# New_Multirotor_CPU_imu_V1_2.net
KiCad netlist of a schematic drawn in EAGLE
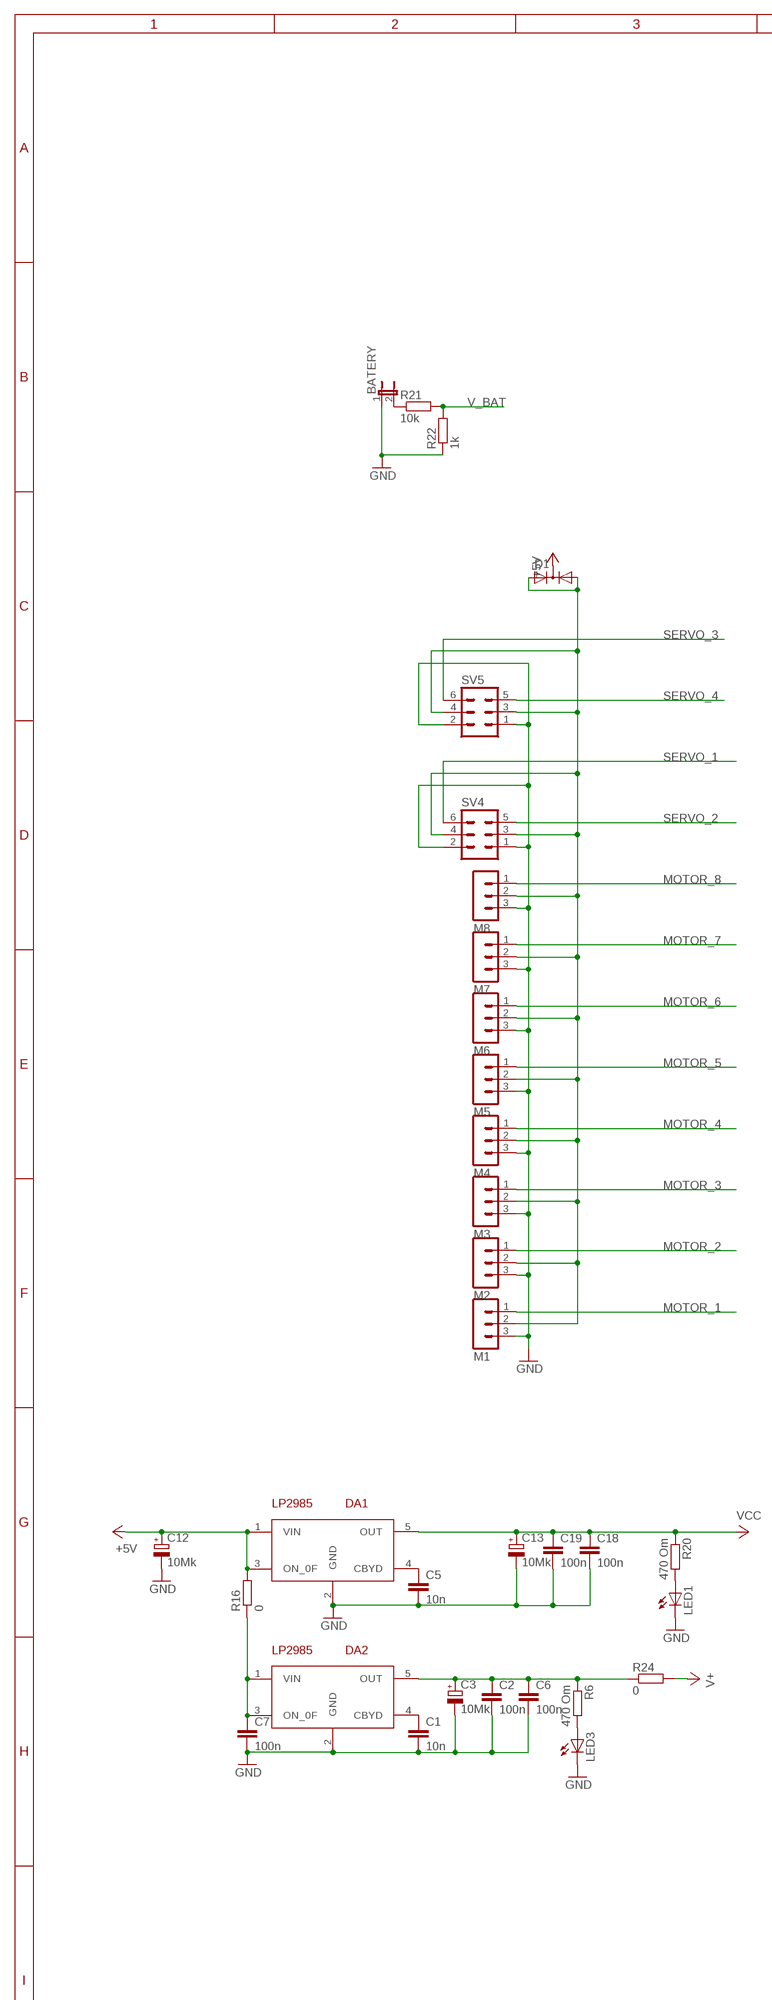
[diagram p0: schematic, sheet 1, part 1 of 2]
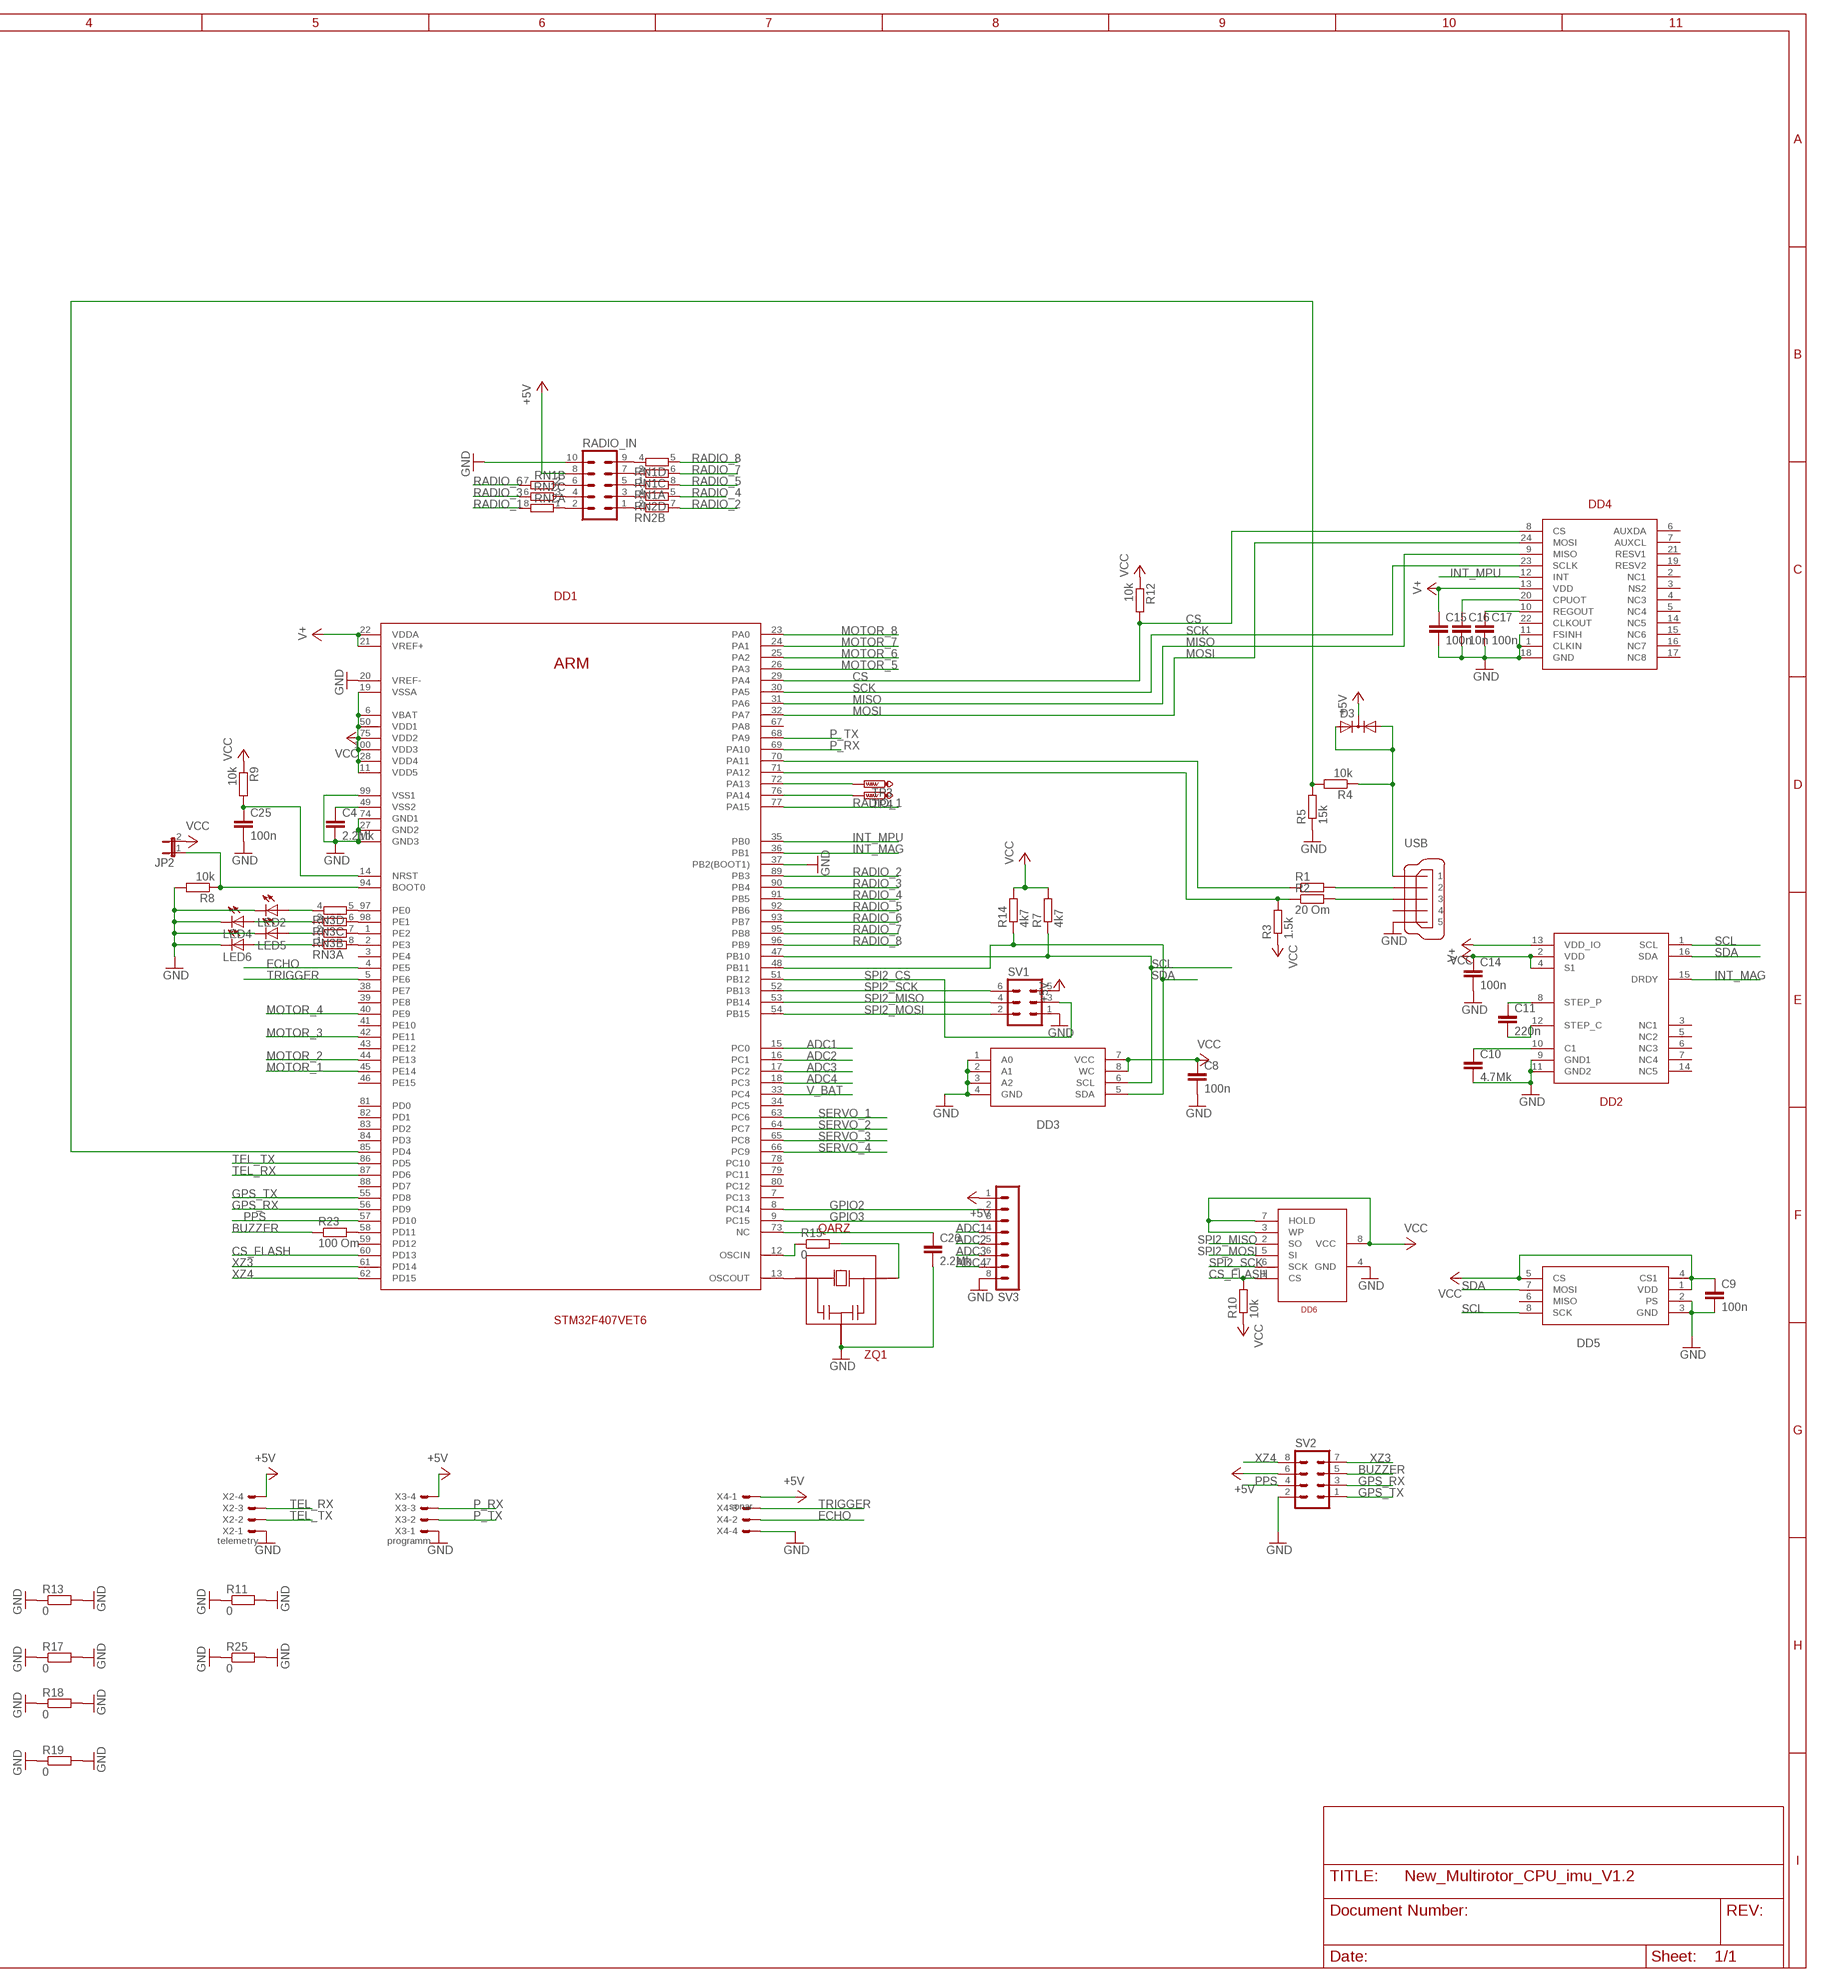
[diagram p1: schematic, sheet 1, part 2 of 2]

(export (version "E")
  (design (tool "Eeschema 10.0.6"))
  (components
    (comp (ref "BATERY")
      (value "JP1E")
      (footprint "eagle-import:JP1")
      (libsource (lib "eagle-import") (part "JP1E"))
    )
    (comp (ref "C1")
      (value "10n")
      (footprint "eagle-import:C0603K")
      (libsource (lib "eagle-import") (part "C-EUC0603K"))
    )
    (comp (ref "C2")
      (value "100n")
      (footprint "eagle-import:C0603K")
      (libsource (lib "eagle-import") (part "C-EUC0603K"))
    )
    (comp (ref "C3")
      (value "10Mk")
      (footprint "eagle-import:A_3216-18W")
      (libsource (lib "eagle-import") (part "CPOL-EUA/3216-18W"))
    )
    (comp (ref "C4")
      (value "2.2Mk")
      (footprint "eagle-import:C0603K")
      (libsource (lib "eagle-import") (part "C-EUC0603K"))
    )
    (comp (ref "C5")
      (value "10n")
      (footprint "eagle-import:C0603K")
      (libsource (lib "eagle-import") (part "C-EUC0603K"))
    )
    (comp (ref "C6")
      (value "100n")
      (footprint "eagle-import:C0603K")
      (libsource (lib "eagle-import") (part "C-EUC0603K"))
    )
    (comp (ref "C7")
      (value "100n")
      (footprint "eagle-import:C0603K")
      (libsource (lib "eagle-import") (part "C-EUC0603K"))
    )
    (comp (ref "C8")
      (value "100n")
      (footprint "eagle-import:C0603K")
      (libsource (lib "eagle-import") (part "C-EUC0603K"))
    )
    (comp (ref "C9")
      (value "100n")
      (footprint "eagle-import:C0603K")
      (libsource (lib "eagle-import") (part "C-EUC0603K"))
    )
    (comp (ref "C10")
      (value "4.7Mk")
      (footprint "eagle-import:C0603K")
      (libsource (lib "eagle-import") (part "C-EUC0603K"))
    )
    (comp (ref "C11")
      (value "220n")
      (footprint "eagle-import:C0603K")
      (libsource (lib "eagle-import") (part "C-EUC0603K"))
    )
    (comp (ref "C12")
      (value "10Mk")
      (footprint "eagle-import:A_3216-18W")
      (libsource (lib "eagle-import") (part "CPOL-EUA/3216-18W"))
    )
    (comp (ref "C13")
      (value "10Mk")
      (footprint "eagle-import:A_3216-18W")
      (libsource (lib "eagle-import") (part "CPOL-EUA/3216-18W"))
    )
    (comp (ref "C14")
      (value "100n")
      (footprint "eagle-import:C0603K")
      (libsource (lib "eagle-import") (part "C-EUC0603K"))
    )
    (comp (ref "C15")
      (value "100n")
      (footprint "eagle-import:C0603K")
      (libsource (lib "eagle-import") (part "C-EUC0603K"))
    )
    (comp (ref "C16")
      (value "10n")
      (footprint "eagle-import:C0603K")
      (libsource (lib "eagle-import") (part "C-EUC0603K"))
    )
    (comp (ref "C17")
      (value "100n")
      (footprint "eagle-import:C0603K")
      (libsource (lib "eagle-import") (part "C-EUC0603K"))
    )
    (comp (ref "C18")
      (value "100n")
      (footprint "eagle-import:C0603K")
      (libsource (lib "eagle-import") (part "C-EUC0603K"))
    )
    (comp (ref "C19")
      (value "100n")
      (footprint "eagle-import:C0603K")
      (libsource (lib "eagle-import") (part "C-EUC0603K"))
    )
    (comp (ref "C25")
      (value "100n")
      (footprint "eagle-import:C0603K")
      (libsource (lib "eagle-import") (part "C-EUC0603K"))
    )
    (comp (ref "C26")
      (value "2.2Mk")
      (footprint "eagle-import:C0603K")
      (libsource (lib "eagle-import") (part "C-EUC0603K"))
    )
    (comp (ref "D1")
      (value "DIODE-2AC|CASOT23")
      (footprint "eagle-import:SOT23")
      (libsource (lib "eagle-import") (part "DIODE-2AC|CASOT23"))
    )
    (comp (ref "D3")
      (value "DIODE-2AC|CASOT23")
      (footprint "eagle-import:SOT23")
      (libsource (lib "eagle-import") (part "DIODE-2AC|CASOT23"))
    )
    (comp (ref "DA1")
      (value "LP2985")
      (footprint "eagle-import:SOT23-5L")
      (libsource (lib "eagle-import") (part "3.3"))
    )
    (comp (ref "DA2")
      (value "LP2985")
      (footprint "eagle-import:SOT23-5L")
      (libsource (lib "eagle-import") (part "3.3"))
    )
    (comp (ref "DD1")
      (value "STM32F407VET6")
      (footprint "eagle-import:LQFP100")
      (libsource (lib "eagle-import") (part "STM32F407VET6"))
    )
    (comp (ref "DD2")
      (value "HMC5883L")
      (footprint "eagle-import:LCC-16")
      (libsource (lib "eagle-import") (part "HMC5883L"))
    )
    (comp (ref "DD3")
      (value "24C512")
      (footprint "eagle-import:SOIC8")
      (libsource (lib "eagle-import") (part "24C512"))
    )
    (comp (ref "DD4")
      (value "MPU6000")
      (footprint "eagle-import:JEDEC")
      (libsource (lib "eagle-import") (part "MPU6000"))
    )
    (comp (ref "DD5")
      (value "MS5611-01BA03")
      (footprint "eagle-import:MS5611-01BA03")
      (libsource (lib "eagle-import") (part "MS5611-01BA03"))
    )
    (comp (ref "DD6")
      (value "W25X40")
      (footprint "eagle-import:SOIC8")
      (libsource (lib "eagle-import") (part "W25X40"))
    )
    (comp (ref "JP2")
      (value "JP1E")
      (footprint "eagle-import:JP1")
      (libsource (lib "eagle-import") (part "JP1E"))
    )
    (comp (ref "LED1")
      (value "LEDCHIPLED_0603")
      (footprint "eagle-import:CHIPLED_0603")
      (libsource (lib "eagle-import") (part "LEDCHIPLED_0603"))
    )
    (comp (ref "LED2")
      (value "LEDCHIPLED_0603")
      (footprint "eagle-import:CHIPLED_0603")
      (libsource (lib "eagle-import") (part "LEDCHIPLED_0603"))
    )
    (comp (ref "LED3")
      (value "LEDCHIPLED_0603")
      (footprint "eagle-import:CHIPLED_0603")
      (libsource (lib "eagle-import") (part "LEDCHIPLED_0603"))
    )
    (comp (ref "LED4")
      (value "LEDCHIPLED_0603")
      (footprint "eagle-import:CHIPLED_0603")
      (libsource (lib "eagle-import") (part "LEDCHIPLED_0603"))
    )
    (comp (ref "LED5")
      (value "LEDCHIPLED_0603")
      (footprint "eagle-import:CHIPLED_0603")
      (libsource (lib "eagle-import") (part "LEDCHIPLED_0603"))
    )
    (comp (ref "LED6")
      (value "LEDCHIPLED_0603")
      (footprint "eagle-import:CHIPLED_0603")
      (libsource (lib "eagle-import") (part "LEDCHIPLED_0603"))
    )
    (comp (ref "M1")
      (value "MA03-1")
      (footprint "eagle-import:MA03-1")
      (fields (field (name "OC_FARNELL") "unknown") (field (name "OC_NEWARK") "unknown"))
      (libsource (lib "eagle-import") (part "MA03-1"))
    )
    (comp (ref "M2")
      (value "MA03-1")
      (footprint "eagle-import:MA03-1")
      (fields (field (name "OC_FARNELL") "unknown") (field (name "OC_NEWARK") "unknown"))
      (libsource (lib "eagle-import") (part "MA03-1"))
    )
    (comp (ref "M3")
      (value "MA03-1")
      (footprint "eagle-import:MA03-1")
      (fields (field (name "OC_FARNELL") "unknown") (field (name "OC_NEWARK") "unknown"))
      (libsource (lib "eagle-import") (part "MA03-1"))
    )
    (comp (ref "M4")
      (value "MA03-1")
      (footprint "eagle-import:MA03-1")
      (fields (field (name "OC_FARNELL") "unknown") (field (name "OC_NEWARK") "unknown"))
      (libsource (lib "eagle-import") (part "MA03-1"))
    )
    (comp (ref "M5")
      (value "MA03-1")
      (footprint "eagle-import:MA03-1")
      (fields (field (name "OC_FARNELL") "unknown") (field (name "OC_NEWARK") "unknown"))
      (libsource (lib "eagle-import") (part "MA03-1"))
    )
    (comp (ref "M6")
      (value "MA03-1")
      (footprint "eagle-import:MA03-1")
      (fields (field (name "OC_FARNELL") "unknown") (field (name "OC_NEWARK") "unknown"))
      (libsource (lib "eagle-import") (part "MA03-1"))
    )
    (comp (ref "M7")
      (value "MA03-1")
      (footprint "eagle-import:MA03-1")
      (fields (field (name "OC_FARNELL") "unknown") (field (name "OC_NEWARK") "unknown"))
      (libsource (lib "eagle-import") (part "MA03-1"))
    )
    (comp (ref "M8")
      (value "MA03-1")
      (footprint "eagle-import:MA03-1")
      (fields (field (name "OC_FARNELL") "unknown") (field (name "OC_NEWARK") "unknown"))
      (libsource (lib "eagle-import") (part "MA03-1"))
    )
    (comp (ref "R1")
      (value "R-EU_R0603")
      (footprint "eagle-import:R0603")
      (libsource (lib "eagle-import") (part "R-EU_R0603"))
    )
    (comp (ref "R2")
      (value "20 Om")
      (footprint "eagle-import:R0603")
      (libsource (lib "eagle-import") (part "R-EU_R0603"))
    )
    (comp (ref "R3")
      (value "1.5k")
      (footprint "eagle-import:R0603")
      (libsource (lib "eagle-import") (part "R-EU_R0603"))
    )
    (comp (ref "R4")
      (value "10k")
      (footprint "eagle-import:R0603")
      (libsource (lib "eagle-import") (part "R-EU_R0603"))
    )
    (comp (ref "R5")
      (value "15k")
      (footprint "eagle-import:R0603")
      (libsource (lib "eagle-import") (part "R-EU_R0603"))
    )
    (comp (ref "R6")
      (value "470 Om")
      (footprint "eagle-import:R0603")
      (libsource (lib "eagle-import") (part "R-EU_R0603"))
    )
    (comp (ref "R7")
      (value "4k7")
      (footprint "eagle-import:R0603")
      (libsource (lib "eagle-import") (part "R-EU_R0603"))
    )
    (comp (ref "R8")
      (value "10k")
      (footprint "eagle-import:R0603")
      (libsource (lib "eagle-import") (part "R-EU_R0603"))
    )
    (comp (ref "R9")
      (value "10k")
      (footprint "eagle-import:R0603")
      (libsource (lib "eagle-import") (part "R-EU_R0603"))
    )
    (comp (ref "R10")
      (value "10k")
      (footprint "eagle-import:R0603")
      (libsource (lib "eagle-import") (part "R-EU_R0603"))
    )
    (comp (ref "R11")
      (value "0")
      (footprint "eagle-import:R0603")
      (libsource (lib "eagle-import") (part "R-EU_R0603"))
    )
    (comp (ref "R12")
      (value "10k")
      (footprint "eagle-import:R0603")
      (libsource (lib "eagle-import") (part "R-EU_R0603"))
    )
    (comp (ref "R13")
      (value "0")
      (footprint "eagle-import:R0603")
      (libsource (lib "eagle-import") (part "R-EU_R0603"))
    )
    (comp (ref "R14")
      (value "4k7")
      (footprint "eagle-import:R0603")
      (libsource (lib "eagle-import") (part "R-EU_R0603"))
    )
    (comp (ref "R15")
      (value "0")
      (footprint "eagle-import:R0603")
      (libsource (lib "eagle-import") (part "R-EU_R0603"))
    )
    (comp (ref "R16")
      (value "0")
      (footprint "eagle-import:R0603")
      (libsource (lib "eagle-import") (part "R-EU_R0603"))
    )
    (comp (ref "R17")
      (value "0")
      (footprint "eagle-import:R0603")
      (libsource (lib "eagle-import") (part "R-EU_R0603"))
    )
    (comp (ref "R18")
      (value "0")
      (footprint "eagle-import:R0603")
      (libsource (lib "eagle-import") (part "R-EU_R0603"))
    )
    (comp (ref "R19")
      (value "0")
      (footprint "eagle-import:R0603")
      (libsource (lib "eagle-import") (part "R-EU_R0603"))
    )
    (comp (ref "R20")
      (value "470 Om")
      (footprint "eagle-import:R0603")
      (libsource (lib "eagle-import") (part "R-EU_R0603"))
    )
    (comp (ref "R21")
      (value "10k")
      (footprint "eagle-import:R0603")
      (libsource (lib "eagle-import") (part "R-EU_R0603"))
    )
    (comp (ref "R22")
      (value "1k")
      (footprint "eagle-import:R0603")
      (libsource (lib "eagle-import") (part "R-EU_R0603"))
    )
    (comp (ref "R23")
      (value "100 Om")
      (footprint "eagle-import:R0603")
      (libsource (lib "eagle-import") (part "R-EU_R0603"))
    )
    (comp (ref "R24")
      (value "0")
      (footprint "eagle-import:R0603")
      (libsource (lib "eagle-import") (part "R-EU_R0603"))
    )
    (comp (ref "R25")
      (value "0")
      (footprint "eagle-import:R0603")
      (libsource (lib "eagle-import") (part "R-EU_R0603"))
    )
    (comp (ref "RADIO_IN")
      (value "MA05-2")
      (footprint "eagle-import:MA05-2")
      (libsource (lib "eagle-import") (part "MA05-2"))
    )
    (comp (ref "RN1")
      (value "4R-N0603-ARV")
      (footprint "eagle-import:0603-ARV")
      (libsource (lib "eagle-import") (part "4R-N0603-ARV"))
    )
    (comp (ref "RN2")
      (value "4R-N0603-ARV")
      (footprint "eagle-import:0603-ARV")
      (libsource (lib "eagle-import") (part "4R-N0603-ARV"))
    )
    (comp (ref "RN3")
      (value "4R-N0603-ARV")
      (footprint "eagle-import:0603-ARV")
      (libsource (lib "eagle-import") (part "4R-N0603-ARV"))
    )
    (comp (ref "SV1")
      (value "MA03-2")
      (footprint "eagle-import:MA03-2")
      (libsource (lib "eagle-import") (part "MA03-2"))
    )
    (comp (ref "SV2")
      (value "MA04-2")
      (footprint "eagle-import:MA04-2")
      (libsource (lib "eagle-import") (part "MA04-2"))
    )
    (comp (ref "SV3")
      (value "MA08-1")
      (footprint "eagle-import:MA08-1")
      (libsource (lib "eagle-import") (part "MA08-1"))
    )
    (comp (ref "SV4")
      (value "MA03-2")
      (footprint "eagle-import:MA03-2")
      (libsource (lib "eagle-import") (part "MA03-2"))
    )
    (comp (ref "SV5")
      (value "MA03-2")
      (footprint "eagle-import:MA03-2")
      (libsource (lib "eagle-import") (part "MA03-2"))
    )
    (comp (ref "TP3")
      (value "PTR1TP12R")
      (footprint "eagle-import:TP12R")
      (libsource (lib "eagle-import") (part "PTR1TP12R"))
    )
    (comp (ref "TP4")
      (value "PTR1TP12R")
      (footprint "eagle-import:TP12R")
      (libsource (lib "eagle-import") (part "PTR1TP12R"))
    )
    (comp (ref "USB")
      (value "MINI-USB-32005-201")
      (footprint "eagle-import:32005-201")
      (libsource (lib "eagle-import") (part "MINI-USB-32005-201"))
    )
    (comp (ref "X2")
      (value "telemetry")
      (footprint "eagle-import:SM04B-SRSS-TB")
      (libsource (lib "eagle-import") (part "?M04B-SRSS-TBS"))
    )
    (comp (ref "X3")
      (value "programm")
      (footprint "eagle-import:SM04B-SRSS-TB")
      (libsource (lib "eagle-import") (part "?M04B-SRSS-TBS"))
    )
    (comp (ref "X4")
      (value "sonar")
      (footprint "eagle-import:SM04B-SRSS-TB")
      (libsource (lib "eagle-import") (part "?M04B-SRSS-TBS"))
    )
    (comp (ref "ZQ1")
      (value "QARZ")
      (footprint "eagle-import:QARZ")
      (libsource (lib "eagle-import") (part "QARZ"))
    )
  )
  (nets
    (net (code "1") (name "+5V") (class "Default")
      (node (ref "C12") (pin "+") (pinfunction "+_+") (pintype "passive"))
      (node (ref "D1") (pin "3") (pinfunction "C_3") (pintype "passive"))
      (node (ref "D3") (pin "3") (pinfunction "C_3") (pintype "passive"))
      (node (ref "DA1") (pin "1") (pinfunction "VIN_1") (pintype "bidirectional"))
      (node (ref "DA1") (pin "3") (pinfunction "ON_0F_3") (pintype "bidirectional"))
      (node (ref "R16") (pin "2") (pinfunction "2_2") (pintype "passive"))
      (node (ref "RADIO_IN") (pin "8") (pinfunction "8_8") (pintype "passive"))
      (node (ref "SV1") (pin "5") (pinfunction "5_5") (pintype "passive"))
      (node (ref "SV2") (pin "6") (pinfunction "6_6") (pintype "passive"))
      (node (ref "SV3") (pin "1") (pinfunction "1_1") (pintype "passive"))
      (node (ref "X2") (pin "4") (pinfunction "S_4") (pintype "passive"))
      (node (ref "X3") (pin "4") (pinfunction "S_4") (pintype "passive"))
      (node (ref "X4") (pin "1") (pinfunction "S_1") (pintype "passive"))
    )
    (net (code "2") (name "/ADC1") (class "Default")
      (node (ref "DD1") (pin "15") (pinfunction "PC0_15") (pintype "bidirectional"))
      (node (ref "SV3") (pin "4") (pinfunction "4_4") (pintype "passive"))
    )
    (net (code "3") (name "/ADC2") (class "Default")
      (node (ref "DD1") (pin "16") (pinfunction "PC1_16") (pintype "bidirectional"))
      (node (ref "SV3") (pin "5") (pinfunction "5_5") (pintype "passive"))
    )
    (net (code "4") (name "/ADC3") (class "Default")
      (node (ref "DD1") (pin "17") (pinfunction "PC2_17") (pintype "bidirectional"))
      (node (ref "SV3") (pin "6") (pinfunction "6_6") (pintype "passive"))
    )
    (net (code "5") (name "/ADC4") (class "Default")
      (node (ref "DD1") (pin "18") (pinfunction "PC3_18") (pintype "bidirectional"))
      (node (ref "SV3") (pin "7") (pinfunction "7_7") (pintype "passive"))
    )
    (net (code "6") (name "/BUZZER") (class "Default")
      (node (ref "R23") (pin "1") (pinfunction "1_1") (pintype "passive"))
      (node (ref "SV2") (pin "5") (pinfunction "5_5") (pintype "passive"))
    )
    (net (code "7") (name "/CS") (class "Default")
      (node (ref "DD1") (pin "29") (pinfunction "PA4_29") (pintype "bidirectional"))
      (node (ref "DD4") (pin "8") (pinfunction "CS_8") (pintype "bidirectional"))
      (node (ref "R12") (pin "2") (pinfunction "2_2") (pintype "passive"))
    )
    (net (code "8") (name "/CS_FLASH") (class "Default")
      (node (ref "DD1") (pin "60") (pinfunction "PD13_60") (pintype "bidirectional"))
      (node (ref "DD6") (pin "1") (pinfunction "CS_1") (pintype "bidirectional"))
      (node (ref "R10") (pin "2") (pinfunction "2_2") (pintype "passive"))
    )
    (net (code "9") (name "/ECHO") (class "Default")
      (node (ref "DD1") (pin "4") (pinfunction "PE5_4") (pintype "bidirectional"))
      (node (ref "X4") (pin "2") (pinfunction "S_2") (pintype "passive"))
    )
    (net (code "10") (name "/GPIO2") (class "Default")
      (node (ref "DD1") (pin "8") (pinfunction "PC14_8") (pintype "bidirectional"))
      (node (ref "SV3") (pin "2") (pinfunction "2_2") (pintype "passive"))
    )
    (net (code "11") (name "/GPIO3") (class "Default")
      (node (ref "DD1") (pin "9") (pinfunction "PC15_9") (pintype "bidirectional"))
      (node (ref "SV3") (pin "3") (pinfunction "3_3") (pintype "passive"))
    )
    (net (code "12") (name "/GPS_RX") (class "Default")
      (node (ref "DD1") (pin "56") (pinfunction "PD9_56") (pintype "bidirectional"))
      (node (ref "SV2") (pin "3") (pinfunction "3_3") (pintype "passive"))
    )
    (net (code "13") (name "/GPS_TX") (class "Default")
      (node (ref "DD1") (pin "55") (pinfunction "PD8_55") (pintype "bidirectional"))
      (node (ref "SV2") (pin "1") (pinfunction "1_1") (pintype "passive"))
    )
    (net (code "14") (name "/INT_MAG") (class "Default")
      (node (ref "DD1") (pin "36") (pinfunction "PB1_36") (pintype "bidirectional"))
      (node (ref "DD2") (pin "15") (pinfunction "DRDY_15") (pintype "bidirectional"))
    )
    (net (code "15") (name "/INT_MPU") (class "Default")
      (node (ref "DD1") (pin "35") (pinfunction "PB0_35") (pintype "bidirectional"))
      (node (ref "DD4") (pin "12") (pinfunction "INT_12") (pintype "bidirectional"))
    )
    (net (code "16") (name "/MISO") (class "Default")
      (node (ref "DD1") (pin "31") (pinfunction "PA6_31") (pintype "bidirectional"))
      (node (ref "DD4") (pin "9") (pinfunction "MISO_9") (pintype "bidirectional"))
    )
    (net (code "17") (name "/MOSI") (class "Default")
      (node (ref "DD1") (pin "32") (pinfunction "PA7_32") (pintype "bidirectional"))
      (node (ref "DD4") (pin "24") (pinfunction "MOSI_24") (pintype "bidirectional"))
    )
    (net (code "18") (name "/MOTOR_1") (class "Default")
      (node (ref "DD1") (pin "45") (pinfunction "PE14_45") (pintype "bidirectional"))
      (node (ref "M1") (pin "1") (pinfunction "1_1") (pintype "passive"))
    )
    (net (code "19") (name "/MOTOR_2") (class "Default")
      (node (ref "DD1") (pin "44") (pinfunction "PE13_44") (pintype "bidirectional"))
      (node (ref "M2") (pin "1") (pinfunction "1_1") (pintype "passive"))
    )
    (net (code "20") (name "/MOTOR_3") (class "Default")
      (node (ref "DD1") (pin "42") (pinfunction "PE11_42") (pintype "bidirectional"))
      (node (ref "M3") (pin "1") (pinfunction "1_1") (pintype "passive"))
    )
    (net (code "21") (name "/MOTOR_4") (class "Default")
      (node (ref "DD1") (pin "40") (pinfunction "PE9_40") (pintype "bidirectional"))
      (node (ref "M4") (pin "1") (pinfunction "1_1") (pintype "passive"))
    )
    (net (code "22") (name "/MOTOR_5") (class "Default")
      (node (ref "DD1") (pin "26") (pinfunction "PA3_26") (pintype "bidirectional"))
      (node (ref "M5") (pin "1") (pinfunction "1_1") (pintype "passive"))
    )
    (net (code "23") (name "/MOTOR_6") (class "Default")
      (node (ref "DD1") (pin "25") (pinfunction "PA2_25") (pintype "bidirectional"))
      (node (ref "M6") (pin "1") (pinfunction "1_1") (pintype "passive"))
    )
    (net (code "24") (name "/MOTOR_7") (class "Default")
      (node (ref "DD1") (pin "24") (pinfunction "PA1_24") (pintype "bidirectional"))
      (node (ref "M7") (pin "1") (pinfunction "1_1") (pintype "passive"))
    )
    (net (code "25") (name "/MOTOR_8") (class "Default")
      (node (ref "DD1") (pin "23") (pinfunction "PA0_23") (pintype "bidirectional"))
      (node (ref "M8") (pin "1") (pinfunction "1_1") (pintype "passive"))
    )
    (net (code "26") (name "/PPS") (class "Default")
      (node (ref "DD1") (pin "57") (pinfunction "PD10_57") (pintype "bidirectional"))
      (node (ref "SV2") (pin "4") (pinfunction "4_4") (pintype "passive"))
    )
    (net (code "27") (name "/P_RX") (class "Default")
      (node (ref "DD1") (pin "69") (pinfunction "PA10_69") (pintype "bidirectional"))
      (node (ref "X3") (pin "3") (pinfunction "S_3") (pintype "passive"))
    )
    (net (code "28") (name "/P_TX") (class "Default")
      (node (ref "DD1") (pin "68") (pinfunction "PA9_68") (pintype "bidirectional"))
      (node (ref "X3") (pin "2") (pinfunction "S_2") (pintype "passive"))
    )
    (net (code "29") (name "/RADIO_1") (class "Default")
      (node (ref "DD1") (pin "77") (pinfunction "PA15_77") (pintype "bidirectional"))
      (node (ref "RN2") (pin "8") (pinfunction "2_8") (pintype "passive"))
    )
    (net (code "30") (name "/RADIO_2") (class "Default")
      (node (ref "DD1") (pin "89") (pinfunction "PB3_89") (pintype "bidirectional"))
      (node (ref "RN2") (pin "7") (pinfunction "2_7") (pintype "passive"))
    )
    (net (code "31") (name "/RADIO_3") (class "Default")
      (node (ref "DD1") (pin "90") (pinfunction "PB4_90") (pintype "bidirectional"))
      (node (ref "RN2") (pin "6") (pinfunction "2_6") (pintype "passive"))
    )
    (net (code "32") (name "/RADIO_4") (class "Default")
      (node (ref "DD1") (pin "91") (pinfunction "PB5_91") (pintype "bidirectional"))
      (node (ref "RN2") (pin "5") (pinfunction "2_5") (pintype "passive"))
    )
    (net (code "33") (name "/RADIO_5") (class "Default")
      (node (ref "DD1") (pin "92") (pinfunction "PB6_92") (pintype "bidirectional"))
      (node (ref "RN1") (pin "8") (pinfunction "2_8") (pintype "passive"))
    )
    (net (code "34") (name "/RADIO_6") (class "Default")
      (node (ref "DD1") (pin "93") (pinfunction "PB7_93") (pintype "bidirectional"))
      (node (ref "RN1") (pin "7") (pinfunction "2_7") (pintype "passive"))
    )
    (net (code "35") (name "/RADIO_7") (class "Default")
      (node (ref "DD1") (pin "95") (pinfunction "PB8_95") (pintype "bidirectional"))
      (node (ref "RN1") (pin "6") (pinfunction "2_6") (pintype "passive"))
    )
    (net (code "36") (name "/RADIO_8") (class "Default")
      (node (ref "DD1") (pin "96") (pinfunction "PB9_96") (pintype "bidirectional"))
      (node (ref "RN1") (pin "5") (pinfunction "2_5") (pintype "passive"))
    )
    (net (code "37") (name "/SCK") (class "Default")
      (node (ref "DD1") (pin "30") (pinfunction "PA5_30") (pintype "bidirectional"))
      (node (ref "DD4") (pin "23") (pinfunction "SCLK_23") (pintype "bidirectional"))
    )
    (net (code "38") (name "/SCL") (class "Default")
      (node (ref "DD1") (pin "47") (pinfunction "PB10_47") (pintype "bidirectional"))
      (node (ref "DD2") (pin "1") (pinfunction "SCL_1") (pintype "bidirectional"))
      (node (ref "DD3") (pin "6") (pinfunction "SCL_6") (pintype "bidirectional"))
      (node (ref "DD5") (pin "8") (pinfunction "SCK_8") (pintype "bidirectional"))
      (node (ref "R7") (pin "1") (pinfunction "1_1") (pintype "passive"))
    )
    (net (code "39") (name "/SDA") (class "Default")
      (node (ref "DD1") (pin "48") (pinfunction "PB11_48") (pintype "bidirectional"))
      (node (ref "DD2") (pin "16") (pinfunction "SDA_16") (pintype "bidirectional"))
      (node (ref "DD3") (pin "5") (pinfunction "SDA_5") (pintype "bidirectional"))
      (node (ref "DD5") (pin "7") (pinfunction "MOSI_7") (pintype "bidirectional"))
      (node (ref "R14") (pin "1") (pinfunction "1_1") (pintype "passive"))
    )
    (net (code "40") (name "/SERVO_1") (class "Default")
      (node (ref "DD1") (pin "63") (pinfunction "PC6_63") (pintype "bidirectional"))
      (node (ref "SV4") (pin "6") (pinfunction "6_6") (pintype "passive"))
    )
    (net (code "41") (name "/SERVO_2") (class "Default")
      (node (ref "DD1") (pin "64") (pinfunction "PC7_64") (pintype "bidirectional"))
      (node (ref "SV4") (pin "5") (pinfunction "5_5") (pintype "passive"))
    )
    (net (code "42") (name "/SERVO_3") (class "Default")
      (node (ref "DD1") (pin "65") (pinfunction "PC8_65") (pintype "bidirectional"))
      (node (ref "SV5") (pin "6") (pinfunction "6_6") (pintype "passive"))
    )
    (net (code "43") (name "/SERVO_4") (class "Default")
      (node (ref "DD1") (pin "66") (pinfunction "PC9_66") (pintype "bidirectional"))
      (node (ref "SV5") (pin "5") (pinfunction "5_5") (pintype "passive"))
    )
    (net (code "44") (name "/SPI2_CS") (class "Default")
      (node (ref "DD1") (pin "51") (pinfunction "PB12_51") (pintype "bidirectional"))
      (node (ref "SV1") (pin "3") (pinfunction "3_3") (pintype "passive"))
    )
    (net (code "45") (name "/SPI2_MISO") (class "Default")
      (node (ref "DD1") (pin "53") (pinfunction "PB14_53") (pintype "bidirectional"))
      (node (ref "DD6") (pin "2") (pinfunction "SO_2") (pintype "bidirectional"))
      (node (ref "SV1") (pin "4") (pinfunction "4_4") (pintype "passive"))
    )
    (net (code "46") (name "/SPI2_MOSI") (class "Default")
      (node (ref "DD1") (pin "54") (pinfunction "PB15_54") (pintype "bidirectional"))
      (node (ref "DD6") (pin "5") (pinfunction "SI_5") (pintype "bidirectional"))
      (node (ref "SV1") (pin "2") (pinfunction "2_2") (pintype "passive"))
    )
    (net (code "47") (name "/SPI2_SCK") (class "Default")
      (node (ref "DD1") (pin "52") (pinfunction "PB13_52") (pintype "bidirectional"))
      (node (ref "DD6") (pin "6") (pinfunction "SCK_6") (pintype "bidirectional"))
      (node (ref "SV1") (pin "6") (pinfunction "6_6") (pintype "passive"))
    )
    (net (code "48") (name "/TEL_RX") (class "Default")
      (node (ref "DD1") (pin "87") (pinfunction "PD6_87") (pintype "bidirectional"))
      (node (ref "X2") (pin "3") (pinfunction "S_3") (pintype "passive"))
    )
    (net (code "49") (name "/TEL_TX") (class "Default")
      (node (ref "DD1") (pin "86") (pinfunction "PD5_86") (pintype "bidirectional"))
      (node (ref "X2") (pin "2") (pinfunction "S_2") (pintype "passive"))
    )
    (net (code "50") (name "/TRIGGER") (class "Default")
      (node (ref "DD1") (pin "5") (pinfunction "PE6_5") (pintype "bidirectional"))
      (node (ref "X4") (pin "3") (pinfunction "S_3") (pintype "passive"))
    )
    (net (code "51") (name "/V_BAT") (class "Default")
      (node (ref "DD1") (pin "33") (pinfunction "PC4_33") (pintype "bidirectional"))
      (node (ref "R21") (pin "2") (pinfunction "2_2") (pintype "passive"))
      (node (ref "R22") (pin "2") (pinfunction "2_2") (pintype "passive"))
    )
    (net (code "52") (name "/XZ3") (class "Default")
      (node (ref "DD1") (pin "61") (pinfunction "PD14_61") (pintype "bidirectional"))
      (node (ref "SV2") (pin "7") (pinfunction "7_7") (pintype "passive"))
    )
    (net (code "53") (name "/XZ4") (class "Default")
      (node (ref "DD1") (pin "62") (pinfunction "PD15_62") (pintype "bidirectional"))
      (node (ref "SV2") (pin "8") (pinfunction "8_8") (pintype "passive"))
    )
    (net (code "54") (name "GND") (class "Default")
      (node (ref "BATERY") (pin "1") (pinfunction "1_1") (pintype "passive"))
      (node (ref "C1") (pin "2") (pinfunction "2_2") (pintype "passive"))
      (node (ref "C10") (pin "2") (pinfunction "2_2") (pintype "passive"))
      (node (ref "C12") (pin "-") (pinfunction "-_-") (pintype "passive"))
      (node (ref "C13") (pin "-") (pinfunction "-_-") (pintype "passive"))
      (node (ref "C14") (pin "2") (pinfunction "2_2") (pintype "passive"))
      (node (ref "C15") (pin "2") (pinfunction "2_2") (pintype "passive"))
      (node (ref "C16") (pin "2") (pinfunction "2_2") (pintype "passive"))
      (node (ref "C17") (pin "2") (pinfunction "2_2") (pintype "passive"))
      (node (ref "C18") (pin "2") (pinfunction "2_2") (pintype "passive"))
      (node (ref "C19") (pin "2") (pinfunction "2_2") (pintype "passive"))
      (node (ref "C2") (pin "2") (pinfunction "2_2") (pintype "passive"))
      (node (ref "C25") (pin "2") (pinfunction "2_2") (pintype "passive"))
      (node (ref "C26") (pin "2") (pinfunction "2_2") (pintype "passive"))
      (node (ref "C3") (pin "-") (pinfunction "-_-") (pintype "passive"))
      (node (ref "C4") (pin "2") (pinfunction "2_2") (pintype "passive"))
      (node (ref "C5") (pin "2") (pinfunction "2_2") (pintype "passive"))
      (node (ref "C6") (pin "2") (pinfunction "2_2") (pintype "passive"))
      (node (ref "C7") (pin "2") (pinfunction "2_2") (pintype "passive"))
      (node (ref "C8") (pin "2") (pinfunction "2_2") (pintype "passive"))
      (node (ref "C9") (pin "2") (pinfunction "2_2") (pintype "passive"))
      (node (ref "DA1") (pin "2") (pinfunction "GND_2") (pintype "bidirectional"))
      (node (ref "DA2") (pin "2") (pinfunction "GND_2") (pintype "bidirectional"))
      (node (ref "DD1") (pin "10") (pinfunction "GND3_10") (pintype "bidirectional"))
      (node (ref "DD1") (pin "20") (pinfunction "VREF-_20") (pintype "bidirectional"))
      (node (ref "DD1") (pin "27") (pinfunction "GND2_27") (pintype "bidirectional"))
      (node (ref "DD1") (pin "37") (pinfunction "PB2(BOOT1)_37") (pintype "bidirectional"))
      (node (ref "DD1") (pin "74") (pinfunction "GND1_74") (pintype "bidirectional"))
      (node (ref "DD1") (pin "99") (pinfunction "VSS1_99") (pintype "bidirectional"))
      (node (ref "DD2") (pin "11") (pinfunction "GND2_11") (pintype "bidirectional"))
      (node (ref "DD2") (pin "9") (pinfunction "GND1_9") (pintype "bidirectional"))
      (node (ref "DD3") (pin "1") (pinfunction "A0_1") (pintype "bidirectional"))
      (node (ref "DD3") (pin "2") (pinfunction "A1_2") (pintype "bidirectional"))
      (node (ref "DD3") (pin "3") (pinfunction "A2_3") (pintype "bidirectional"))
      (node (ref "DD3") (pin "4") (pinfunction "GND_4") (pintype "bidirectional"))
      (node (ref "DD4") (pin "1") (pinfunction "CLKIN_1") (pintype "bidirectional"))
      (node (ref "DD4") (pin "11") (pinfunction "FSINH_11") (pintype "bidirectional"))
      (node (ref "DD4") (pin "18") (pinfunction "GND_18") (pintype "bidirectional"))
      (node (ref "DD5") (pin "2") (pinfunction "PS_2") (pintype "bidirectional"))
      (node (ref "DD5") (pin "3") (pinfunction "GND_3") (pintype "bidirectional"))
      (node (ref "DD6") (pin "4") (pinfunction "GND_4") (pintype "bidirectional"))
      (node (ref "LED1") (pin "C") (pinfunction "C_C") (pintype "passive"))
      (node (ref "LED2") (pin "C") (pinfunction "C_C") (pintype "passive"))
      (node (ref "LED3") (pin "C") (pinfunction "C_C") (pintype "passive"))
      (node (ref "LED4") (pin "C") (pinfunction "C_C") (pintype "passive"))
      (node (ref "LED5") (pin "C") (pinfunction "C_C") (pintype "passive"))
      (node (ref "LED6") (pin "C") (pinfunction "C_C") (pintype "passive"))
      (node (ref "M1") (pin "3") (pinfunction "3_3") (pintype "passive"))
      (node (ref "M2") (pin "3") (pinfunction "3_3") (pintype "passive"))
      (node (ref "M3") (pin "3") (pinfunction "3_3") (pintype "passive"))
      (node (ref "M4") (pin "3") (pinfunction "3_3") (pintype "passive"))
      (node (ref "M5") (pin "3") (pinfunction "3_3") (pintype "passive"))
      (node (ref "M6") (pin "3") (pinfunction "3_3") (pintype "passive"))
      (node (ref "M7") (pin "3") (pinfunction "3_3") (pintype "passive"))
      (node (ref "M8") (pin "3") (pinfunction "3_3") (pintype "passive"))
      (node (ref "R11") (pin "1") (pinfunction "1_1") (pintype "passive"))
      (node (ref "R11") (pin "2") (pinfunction "2_2") (pintype "passive"))
      (node (ref "R13") (pin "1") (pinfunction "1_1") (pintype "passive"))
      (node (ref "R13") (pin "2") (pinfunction "2_2") (pintype "passive"))
      (node (ref "R17") (pin "1") (pinfunction "1_1") (pintype "passive"))
      (node (ref "R17") (pin "2") (pinfunction "2_2") (pintype "passive"))
      (node (ref "R18") (pin "1") (pinfunction "1_1") (pintype "passive"))
      (node (ref "R18") (pin "2") (pinfunction "2_2") (pintype "passive"))
      (node (ref "R19") (pin "1") (pinfunction "1_1") (pintype "passive"))
      (node (ref "R19") (pin "2") (pinfunction "2_2") (pintype "passive"))
      (node (ref "R22") (pin "1") (pinfunction "1_1") (pintype "passive"))
      (node (ref "R25") (pin "1") (pinfunction "1_1") (pintype "passive"))
      (node (ref "R25") (pin "2") (pinfunction "2_2") (pintype "passive"))
      (node (ref "R5") (pin "1") (pinfunction "1_1") (pintype "passive"))
      (node (ref "R8") (pin "2") (pinfunction "2_2") (pintype "passive"))
      (node (ref "RADIO_IN") (pin "10") (pinfunction "10_10") (pintype "passive"))
      (node (ref "SV1") (pin "1") (pinfunction "1_1") (pintype "passive"))
      (node (ref "SV2") (pin "2") (pinfunction "2_2") (pintype "passive"))
      (node (ref "SV3") (pin "8") (pinfunction "8_8") (pintype "passive"))
      (node (ref "SV4") (pin "1") (pinfunction "1_1") (pintype "passive"))
      (node (ref "SV4") (pin "2") (pinfunction "2_2") (pintype "passive"))
      (node (ref "SV5") (pin "1") (pinfunction "1_1") (pintype "passive"))
      (node (ref "SV5") (pin "2") (pinfunction "2_2") (pintype "passive"))
      (node (ref "USB") (pin "5") (pinfunction "5_5") (pintype "passive"))
      (node (ref "X2") (pin "1") (pinfunction "S_1") (pintype "passive"))
      (node (ref "X3") (pin "1") (pinfunction "S_1") (pintype "passive"))
      (node (ref "X4") (pin "4") (pinfunction "S_4") (pintype "passive"))
      (node (ref "ZQ1") (pin "2") (pinfunction "2_2") (pintype "bidirectional"))
    )
    (net (code "55") (name "Net-(BATERY-Pad2)") (class "Default")
      (node (ref "BATERY") (pin "2") (pinfunction "2_2") (pintype "passive"))
      (node (ref "R21") (pin "1") (pinfunction "1_1") (pintype "passive"))
    )
    (net (code "56") (name "Net-(D1-A1)") (class "Default")
      (node (ref "D1") (pin "1") (pinfunction "A1_1") (pintype "passive"))
      (node (ref "D1") (pin "2") (pinfunction "A2_2") (pintype "passive"))
      (node (ref "M1") (pin "2") (pinfunction "2_2") (pintype "passive"))
      (node (ref "M2") (pin "2") (pinfunction "2_2") (pintype "passive"))
      (node (ref "M3") (pin "2") (pinfunction "2_2") (pintype "passive"))
      (node (ref "M4") (pin "2") (pinfunction "2_2") (pintype "passive"))
      (node (ref "M5") (pin "2") (pinfunction "2_2") (pintype "passive"))
      (node (ref "M6") (pin "2") (pinfunction "2_2") (pintype "passive"))
      (node (ref "M7") (pin "2") (pinfunction "2_2") (pintype "passive"))
      (node (ref "M8") (pin "2") (pinfunction "2_2") (pintype "passive"))
      (node (ref "SV4") (pin "3") (pinfunction "3_3") (pintype "passive"))
      (node (ref "SV4") (pin "4") (pinfunction "4_4") (pintype "passive"))
      (node (ref "SV5") (pin "3") (pinfunction "3_3") (pintype "passive"))
      (node (ref "SV5") (pin "4") (pinfunction "4_4") (pintype "passive"))
    )
    (net (code "57") (name "Net-(D3-A1)") (class "Default")
      (node (ref "D3") (pin "1") (pinfunction "A1_1") (pintype "passive"))
      (node (ref "D3") (pin "2") (pinfunction "A2_2") (pintype "passive"))
      (node (ref "R4") (pin "1") (pinfunction "1_1") (pintype "passive"))
      (node (ref "USB") (pin "1") (pinfunction "1_1") (pintype "passive"))
    )
    (net (code "58") (name "Net-(DA1-CBYD)") (class "Default")
      (node (ref "C5") (pin "1") (pinfunction "1_1") (pintype "passive"))
      (node (ref "DA1") (pin "4") (pinfunction "CBYD_4") (pintype "bidirectional"))
    )
    (net (code "59") (name "Net-(DA2-CBYD)") (class "Default")
      (node (ref "C1") (pin "1") (pinfunction "1_1") (pintype "passive"))
      (node (ref "DA2") (pin "4") (pinfunction "CBYD_4") (pintype "bidirectional"))
    )
    (net (code "60") (name "Net-(DA2-ON_0F)") (class "Default")
      (node (ref "C7") (pin "1") (pinfunction "1_1") (pintype "passive"))
      (node (ref "DA2") (pin "1") (pinfunction "VIN_1") (pintype "bidirectional"))
      (node (ref "DA2") (pin "3") (pinfunction "ON_0F_3") (pintype "bidirectional"))
      (node (ref "R16") (pin "1") (pinfunction "1_1") (pintype "passive"))
    )
    (net (code "61") (name "Net-(DA2-OUT)") (class "Default")
      (node (ref "C2") (pin "1") (pinfunction "1_1") (pintype "passive"))
      (node (ref "C3") (pin "+") (pinfunction "+_+") (pintype "passive"))
      (node (ref "C6") (pin "1") (pinfunction "1_1") (pintype "passive"))
      (node (ref "DA2") (pin "5") (pinfunction "OUT_5") (pintype "bidirectional"))
      (node (ref "R24") (pin "1") (pinfunction "1_1") (pintype "passive"))
      (node (ref "R6") (pin "1") (pinfunction "1_1") (pintype "passive"))
    )
    (net (code "62") (name "Net-(DD1-BOOT0)") (class "Default")
      (node (ref "DD1") (pin "94") (pinfunction "BOOT0_94") (pintype "bidirectional"))
      (node (ref "JP2") (pin "1") (pinfunction "1_1") (pintype "passive"))
      (node (ref "R8") (pin "1") (pinfunction "1_1") (pintype "passive"))
    )
    (net (code "63") (name "Net-(DD1-NC)") (class "Default")
      (node (ref "C26") (pin "1") (pinfunction "1_1") (pintype "passive"))
      (node (ref "DD1") (pin "73") (pinfunction "NC_73") (pintype "bidirectional"))
    )
    (net (code "64") (name "Net-(DD1-NRST)") (class "Default")
      (node (ref "C25") (pin "1") (pinfunction "1_1") (pintype "passive"))
      (node (ref "DD1") (pin "14") (pinfunction "NRST_14") (pintype "bidirectional"))
      (node (ref "R9") (pin "2") (pinfunction "2_2") (pintype "passive"))
    )
    (net (code "65") (name "Net-(DD1-OSCIN)") (class "Default")
      (node (ref "DD1") (pin "12") (pinfunction "OSCIN_12") (pintype "bidirectional"))
      (node (ref "R15") (pin "1") (pinfunction "1_1") (pintype "passive"))
    )
    (net (code "66") (name "Net-(DD1-OSCOUT)") (class "Default")
      (node (ref "DD1") (pin "13") (pinfunction "OSCOUT_13") (pintype "bidirectional"))
      (node (ref "ZQ1") (pin "1") (pinfunction "1_1") (pintype "bidirectional"))
    )
    (net (code "67") (name "Net-(DD1-PA11)") (class "Default")
      (node (ref "DD1") (pin "70") (pinfunction "PA11_70") (pintype "bidirectional"))
      (node (ref "R1") (pin "1") (pinfunction "1_1") (pintype "passive"))
    )
    (net (code "68") (name "Net-(DD1-PA12)") (class "Default")
      (node (ref "DD1") (pin "71") (pinfunction "PA12_71") (pintype "bidirectional"))
      (node (ref "R2") (pin "1") (pinfunction "1_1") (pintype "passive"))
      (node (ref "R3") (pin "2") (pinfunction "2_2") (pintype "passive"))
    )
    (net (code "69") (name "Net-(DD1-PA13)") (class "Default")
      (node (ref "DD1") (pin "72") (pinfunction "PA13_72") (pintype "bidirectional"))
      (node (ref "TP3") (pin "TP") (pinfunction "TP_TP") (pintype "input"))
    )
    (net (code "70") (name "Net-(DD1-PA14)") (class "Default")
      (node (ref "DD1") (pin "76") (pinfunction "PA14_76") (pintype "bidirectional"))
      (node (ref "TP4") (pin "TP") (pinfunction "TP_TP") (pintype "input"))
    )
    (net (code "71") (name "Net-(DD1-PD4)") (class "Default")
      (node (ref "DD1") (pin "85") (pinfunction "PD4_85") (pintype "bidirectional"))
      (node (ref "R4") (pin "2") (pinfunction "2_2") (pintype "passive"))
      (node (ref "R5") (pin "2") (pinfunction "2_2") (pintype "passive"))
    )
    (net (code "72") (name "Net-(DD1-PD11)") (class "Default")
      (node (ref "DD1") (pin "58") (pinfunction "PD11_58") (pintype "bidirectional"))
      (node (ref "R23") (pin "2") (pinfunction "2_2") (pintype "passive"))
    )
    (net (code "73") (name "Net-(DD1-PE0)") (class "Default")
      (node (ref "DD1") (pin "97") (pinfunction "PE0_97") (pintype "bidirectional"))
      (node (ref "RN3") (pin "5") (pinfunction "2_5") (pintype "passive"))
    )
    (net (code "74") (name "Net-(DD1-PE1)") (class "Default")
      (node (ref "DD1") (pin "98") (pinfunction "PE1_98") (pintype "bidirectional"))
      (node (ref "RN3") (pin "6") (pinfunction "2_6") (pintype "passive"))
    )
    (net (code "75") (name "Net-(DD1-PE2)") (class "Default")
      (node (ref "DD1") (pin "1") (pinfunction "PE2_1") (pintype "bidirectional"))
      (node (ref "RN3") (pin "7") (pinfunction "2_7") (pintype "passive"))
    )
    (net (code "76") (name "Net-(DD1-PE3)") (class "Default")
      (node (ref "DD1") (pin "2") (pinfunction "PE3_2") (pintype "bidirectional"))
      (node (ref "RN3") (pin "8") (pinfunction "2_8") (pintype "passive"))
    )
    (net (code "77") (name "Net-(DD1-VSS2)") (class "Default")
      (node (ref "C4") (pin "1") (pinfunction "1_1") (pintype "passive"))
      (node (ref "DD1") (pin "49") (pinfunction "VSS2_49") (pintype "bidirectional"))
    )
    (net (code "78") (name "Net-(DD2-C1)") (class "Default")
      (node (ref "C10") (pin "1") (pinfunction "1_1") (pintype "passive"))
      (node (ref "DD2") (pin "10") (pinfunction "C1_10") (pintype "bidirectional"))
    )
    (net (code "79") (name "Net-(DD2-STEP_C)") (class "Default")
      (node (ref "C11") (pin "2") (pinfunction "2_2") (pintype "passive"))
      (node (ref "DD2") (pin "12") (pinfunction "STEP_C_12") (pintype "bidirectional"))
    )
    (net (code "80") (name "Net-(DD2-STEP_P)") (class "Default")
      (node (ref "C11") (pin "1") (pinfunction "1_1") (pintype "passive"))
      (node (ref "DD2") (pin "8") (pinfunction "STEP_P_8") (pintype "bidirectional"))
    )
    (net (code "81") (name "Net-(DD4-CPUOT)") (class "Default")
      (node (ref "C16") (pin "1") (pinfunction "1_1") (pintype "passive"))
      (node (ref "DD4") (pin "20") (pinfunction "CPUOT_20") (pintype "bidirectional"))
    )
    (net (code "82") (name "Net-(DD4-REGOUT)") (class "Default")
      (node (ref "C17") (pin "1") (pinfunction "1_1") (pintype "passive"))
      (node (ref "DD4") (pin "10") (pinfunction "REGOUT_10") (pintype "bidirectional"))
    )
    (net (code "83") (name "Net-(LED1-PadA)") (class "Default")
      (node (ref "LED1") (pin "A") (pinfunction "A_A") (pintype "passive"))
      (node (ref "R20") (pin "2") (pinfunction "2_2") (pintype "passive"))
    )
    (net (code "84") (name "Net-(LED3-PadA)") (class "Default")
      (node (ref "LED3") (pin "A") (pinfunction "A_A") (pintype "passive"))
      (node (ref "R6") (pin "2") (pinfunction "2_2") (pintype "passive"))
    )
    (net (code "85") (name "Net-(LED6-PadA)") (class "Default")
      (node (ref "LED6") (pin "A") (pinfunction "A_A") (pintype "passive"))
      (node (ref "RN3") (pin "1") (pinfunction "1_1") (pintype "passive"))
    )
    (net (code "86") (name "Net-(R1-Pad2)") (class "Default")
      (node (ref "R1") (pin "2") (pinfunction "2_2") (pintype "passive"))
      (node (ref "USB") (pin "2") (pinfunction "2_2") (pintype "passive"))
    )
    (net (code "87") (name "Net-(R2-Pad2)") (class "Default")
      (node (ref "R2") (pin "2") (pinfunction "2_2") (pintype "passive"))
      (node (ref "USB") (pin "3") (pinfunction "3_3") (pintype "passive"))
    )
    (net (code "88") (name "Net-(R15-Pad2)") (class "Default")
      (node (ref "R15") (pin "2") (pinfunction "2_2") (pintype "passive"))
      (node (ref "ZQ1") (pin "3") (pinfunction "3_3") (pintype "bidirectional"))
    )
    (net (code "89") (name "Net-(RADIO_IN-Pad2)") (class "Default")
      (node (ref "RADIO_IN") (pin "2") (pinfunction "2_2") (pintype "passive"))
      (node (ref "RN2") (pin "1") (pinfunction "1_1") (pintype "passive"))
    )
    (net (code "90") (name "Net-(RADIO_IN-Pad5)") (class "Default")
      (node (ref "RADIO_IN") (pin "5") (pinfunction "5_5") (pintype "passive"))
      (node (ref "RN1") (pin "1") (pinfunction "1_1") (pintype "passive"))
    )
    (net (code "91") (name "Net-(RN1B-1)") (class "Default")
      (node (ref "RADIO_IN") (pin "6") (pinfunction "6_6") (pintype "passive"))
      (node (ref "RN1") (pin "2") (pinfunction "1_2") (pintype "passive"))
    )
    (net (code "92") (name "Net-(RN1C-1)") (class "Default")
      (node (ref "RADIO_IN") (pin "7") (pinfunction "7_7") (pintype "passive"))
      (node (ref "RN1") (pin "3") (pinfunction "1_3") (pintype "passive"))
    )
    (net (code "93") (name "Net-(RN1D-1)") (class "Default")
      (node (ref "RADIO_IN") (pin "9") (pinfunction "9_9") (pintype "passive"))
      (node (ref "RN1") (pin "4") (pinfunction "1_4") (pintype "passive"))
    )
    (net (code "94") (name "Net-(RN2B-1)") (class "Default")
      (node (ref "RADIO_IN") (pin "1") (pinfunction "1_1") (pintype "passive"))
      (node (ref "RN2") (pin "2") (pinfunction "1_2") (pintype "passive"))
    )
    (net (code "95") (name "Net-(RN2C-1)") (class "Default")
      (node (ref "RADIO_IN") (pin "4") (pinfunction "4_4") (pintype "passive"))
      (node (ref "RN2") (pin "3") (pinfunction "1_3") (pintype "passive"))
    )
    (net (code "96") (name "Net-(RN2D-1)") (class "Default")
      (node (ref "RADIO_IN") (pin "3") (pinfunction "3_3") (pintype "passive"))
      (node (ref "RN2") (pin "4") (pinfunction "1_4") (pintype "passive"))
    )
    (net (code "97") (name "Net-(RN3B-1)") (class "Default")
      (node (ref "LED5") (pin "A") (pinfunction "A_A") (pintype "passive"))
      (node (ref "RN3") (pin "2") (pinfunction "1_2") (pintype "passive"))
    )
    (net (code "98") (name "Net-(RN3C-1)") (class "Default")
      (node (ref "LED4") (pin "A") (pinfunction "A_A") (pintype "passive"))
      (node (ref "RN3") (pin "3") (pinfunction "1_3") (pintype "passive"))
    )
    (net (code "99") (name "Net-(RN3D-1)") (class "Default")
      (node (ref "LED2") (pin "A") (pinfunction "A_A") (pintype "passive"))
      (node (ref "RN3") (pin "4") (pinfunction "1_4") (pintype "passive"))
    )
    (net (code "100") (name "V+") (class "Default")
      (node (ref "C14") (pin "1") (pinfunction "1_1") (pintype "passive"))
      (node (ref "C15") (pin "1") (pinfunction "1_1") (pintype "passive"))
      (node (ref "DD1") (pin "21") (pinfunction "VREF+_21") (pintype "bidirectional"))
      (node (ref "DD1") (pin "22") (pinfunction "VDDA_22") (pintype "bidirectional"))
      (node (ref "DD2") (pin "2") (pinfunction "VDD_2") (pintype "bidirectional"))
      (node (ref "DD2") (pin "4") (pinfunction "S1_4") (pintype "bidirectional"))
      (node (ref "DD4") (pin "13") (pinfunction "VDD_13") (pintype "bidirectional"))
      (node (ref "R24") (pin "2") (pinfunction "2_2") (pintype "passive"))
    )
    (net (code "101") (name "VCC") (class "Default")
      (node (ref "C13") (pin "+") (pinfunction "+_+") (pintype "passive"))
      (node (ref "C18") (pin "1") (pinfunction "1_1") (pintype "passive"))
      (node (ref "C19") (pin "1") (pinfunction "1_1") (pintype "passive"))
      (node (ref "C8") (pin "1") (pinfunction "1_1") (pintype "passive"))
      (node (ref "C9") (pin "1") (pinfunction "1_1") (pintype "passive"))
      (node (ref "DA1") (pin "5") (pinfunction "OUT_5") (pintype "bidirectional"))
      (node (ref "DD1") (pin "100") (pinfunction "VDD3_100") (pintype "bidirectional"))
      (node (ref "DD1") (pin "11") (pinfunction "VDD5_11") (pintype "bidirectional"))
      (node (ref "DD1") (pin "19") (pinfunction "VSSA_19") (pintype "bidirectional"))
      (node (ref "DD1") (pin "28") (pinfunction "VDD4_28") (pintype "bidirectional"))
      (node (ref "DD1") (pin "50") (pinfunction "VDD1_50") (pintype "bidirectional"))
      (node (ref "DD1") (pin "6") (pinfunction "VBAT_6") (pintype "bidirectional"))
      (node (ref "DD1") (pin "75") (pinfunction "VDD2_75") (pintype "bidirectional"))
      (node (ref "DD2") (pin "13") (pinfunction "VDD_IO_13") (pintype "bidirectional"))
      (node (ref "DD3") (pin "7") (pinfunction "VCC_7") (pintype "bidirectional"))
      (node (ref "DD3") (pin "8") (pinfunction "WC_8") (pintype "bidirectional"))
      (node (ref "DD5") (pin "1") (pinfunction "VDD_1") (pintype "bidirectional"))
      (node (ref "DD5") (pin "4") (pinfunction "CS1_4") (pintype "bidirectional"))
      (node (ref "DD5") (pin "5") (pinfunction "CS_5") (pintype "bidirectional"))
      (node (ref "DD6") (pin "3") (pinfunction "WP_3") (pintype "bidirectional"))
      (node (ref "DD6") (pin "7") (pinfunction "HOLD_7") (pintype "bidirectional"))
      (node (ref "DD6") (pin "8") (pinfunction "VCC_8") (pintype "bidirectional"))
      (node (ref "JP2") (pin "2") (pinfunction "2_2") (pintype "passive"))
      (node (ref "R10") (pin "1") (pinfunction "1_1") (pintype "passive"))
      (node (ref "R12") (pin "1") (pinfunction "1_1") (pintype "passive"))
      (node (ref "R14") (pin "2") (pinfunction "2_2") (pintype "passive"))
      (node (ref "R20") (pin "1") (pinfunction "1_1") (pintype "passive"))
      (node (ref "R3") (pin "1") (pinfunction "1_1") (pintype "passive"))
      (node (ref "R7") (pin "2") (pinfunction "2_2") (pintype "passive"))
      (node (ref "R9") (pin "1") (pinfunction "1_1") (pintype "passive"))
    )
    (net (code "102") (name "unconnected-(DD1-PA8-Pad67)") (class "Default")
      (node (ref "DD1") (pin "67") (pinfunction "PA8_67") (pintype "bidirectional"))
    )
    (net (code "103") (name "unconnected-(DD1-PC5-Pad34)") (class "Default")
      (node (ref "DD1") (pin "34") (pinfunction "PC5_34") (pintype "bidirectional"))
    )
    (net (code "104") (name "unconnected-(DD1-PC10-Pad78)") (class "Default")
      (node (ref "DD1") (pin "78") (pinfunction "PC10_78") (pintype "bidirectional"))
    )
    (net (code "105") (name "unconnected-(DD1-PC11-Pad79)") (class "Default")
      (node (ref "DD1") (pin "79") (pinfunction "PC11_79") (pintype "bidirectional"))
    )
    (net (code "106") (name "unconnected-(DD1-PC12-Pad80)") (class "Default")
      (node (ref "DD1") (pin "80") (pinfunction "PC12_80") (pintype "bidirectional"))
    )
    (net (code "107") (name "unconnected-(DD1-PC13-Pad7)") (class "Default")
      (node (ref "DD1") (pin "7") (pinfunction "PC13_7") (pintype "bidirectional"))
    )
    (net (code "108") (name "unconnected-(DD1-PD0-Pad81)") (class "Default")
      (node (ref "DD1") (pin "81") (pinfunction "PD0_81") (pintype "bidirectional"))
    )
    (net (code "109") (name "unconnected-(DD1-PD1-Pad82)") (class "Default")
      (node (ref "DD1") (pin "82") (pinfunction "PD1_82") (pintype "bidirectional"))
    )
    (net (code "110") (name "unconnected-(DD1-PD2-Pad83)") (class "Default")
      (node (ref "DD1") (pin "83") (pinfunction "PD2_83") (pintype "bidirectional"))
    )
    (net (code "111") (name "unconnected-(DD1-PD3-Pad84)") (class "Default")
      (node (ref "DD1") (pin "84") (pinfunction "PD3_84") (pintype "bidirectional"))
    )
    (net (code "112") (name "unconnected-(DD1-PD7-Pad88)") (class "Default")
      (node (ref "DD1") (pin "88") (pinfunction "PD7_88") (pintype "bidirectional"))
    )
    (net (code "113") (name "unconnected-(DD1-PD12-Pad59)") (class "Default")
      (node (ref "DD1") (pin "59") (pinfunction "PD12_59") (pintype "bidirectional"))
    )
    (net (code "114") (name "unconnected-(DD1-PE4-Pad3)") (class "Default")
      (node (ref "DD1") (pin "3") (pinfunction "PE4_3") (pintype "bidirectional"))
    )
    (net (code "115") (name "unconnected-(DD1-PE7-Pad38)") (class "Default")
      (node (ref "DD1") (pin "38") (pinfunction "PE7_38") (pintype "bidirectional"))
    )
    (net (code "116") (name "unconnected-(DD1-PE8-Pad39)") (class "Default")
      (node (ref "DD1") (pin "39") (pinfunction "PE8_39") (pintype "bidirectional"))
    )
    (net (code "117") (name "unconnected-(DD1-PE10-Pad41)") (class "Default")
      (node (ref "DD1") (pin "41") (pinfunction "PE10_41") (pintype "bidirectional"))
    )
    (net (code "118") (name "unconnected-(DD1-PE12-Pad43)") (class "Default")
      (node (ref "DD1") (pin "43") (pinfunction "PE12_43") (pintype "bidirectional"))
    )
    (net (code "119") (name "unconnected-(DD1-PE15-Pad46)") (class "Default")
      (node (ref "DD1") (pin "46") (pinfunction "PE15_46") (pintype "bidirectional"))
    )
    (net (code "120") (name "unconnected-(DD2-NC1-Pad3)") (class "Default")
      (node (ref "DD2") (pin "3") (pinfunction "NC1_3") (pintype "bidirectional"))
    )
    (net (code "121") (name "unconnected-(DD2-NC2-Pad5)") (class "Default")
      (node (ref "DD2") (pin "5") (pinfunction "NC2_5") (pintype "bidirectional"))
    )
    (net (code "122") (name "unconnected-(DD2-NC3-Pad6)") (class "Default")
      (node (ref "DD2") (pin "6") (pinfunction "NC3_6") (pintype "bidirectional"))
    )
    (net (code "123") (name "unconnected-(DD2-NC4-Pad7)") (class "Default")
      (node (ref "DD2") (pin "7") (pinfunction "NC4_7") (pintype "bidirectional"))
    )
    (net (code "124") (name "unconnected-(DD2-NC5-Pad14)") (class "Default")
      (node (ref "DD2") (pin "14") (pinfunction "NC5_14") (pintype "bidirectional"))
    )
    (net (code "125") (name "unconnected-(DD4-AUXCL-Pad7)") (class "Default")
      (node (ref "DD4") (pin "7") (pinfunction "AUXCL_7") (pintype "bidirectional"))
    )
    (net (code "126") (name "unconnected-(DD4-AUXDA-Pad6)") (class "Default")
      (node (ref "DD4") (pin "6") (pinfunction "AUXDA_6") (pintype "bidirectional"))
    )
    (net (code "127") (name "unconnected-(DD4-CLKOUT-Pad22)") (class "Default")
      (node (ref "DD4") (pin "22") (pinfunction "CLKOUT_22") (pintype "bidirectional"))
    )
    (net (code "128") (name "unconnected-(DD4-NC1-Pad2)") (class "Default")
      (node (ref "DD4") (pin "2") (pinfunction "NC1_2") (pintype "bidirectional"))
    )
    (net (code "129") (name "unconnected-(DD4-NC3-Pad4)") (class "Default")
      (node (ref "DD4") (pin "4") (pinfunction "NC3_4") (pintype "bidirectional"))
    )
    (net (code "130") (name "unconnected-(DD4-NC4-Pad5)") (class "Default")
      (node (ref "DD4") (pin "5") (pinfunction "NC4_5") (pintype "bidirectional"))
    )
    (net (code "131") (name "unconnected-(DD4-NC5-Pad14)") (class "Default")
      (node (ref "DD4") (pin "14") (pinfunction "NC5_14") (pintype "bidirectional"))
    )
    (net (code "132") (name "unconnected-(DD4-NC6-Pad15)") (class "Default")
      (node (ref "DD4") (pin "15") (pinfunction "NC6_15") (pintype "bidirectional"))
    )
    (net (code "133") (name "unconnected-(DD4-NC7-Pad16)") (class "Default")
      (node (ref "DD4") (pin "16") (pinfunction "NC7_16") (pintype "bidirectional"))
    )
    (net (code "134") (name "unconnected-(DD4-NC8-Pad17)") (class "Default")
      (node (ref "DD4") (pin "17") (pinfunction "NC8_17") (pintype "bidirectional"))
    )
    (net (code "135") (name "unconnected-(DD4-NS2-Pad3)") (class "Default")
      (node (ref "DD4") (pin "3") (pinfunction "NS2_3") (pintype "bidirectional"))
    )
    (net (code "136") (name "unconnected-(DD4-RESV1-Pad21)") (class "Default")
      (node (ref "DD4") (pin "21") (pinfunction "RESV1_21") (pintype "bidirectional"))
    )
    (net (code "137") (name "unconnected-(DD4-RESV2-Pad19)") (class "Default")
      (node (ref "DD4") (pin "19") (pinfunction "RESV2_19") (pintype "bidirectional"))
    )
    (net (code "138") (name "unconnected-(DD5-MISO-Pad6)") (class "Default")
      (node (ref "DD5") (pin "6") (pinfunction "MISO_6") (pintype "bidirectional"))
    )
    (net (code "139") (name "unconnected-(USB-Pad4)") (class "Default")
      (node (ref "USB") (pin "4") (pinfunction "4_4") (pintype "passive"))
    )
  )
)
